# UART_CHANGER.net
KiCad netlist of a schematic drawn in Altium Designer
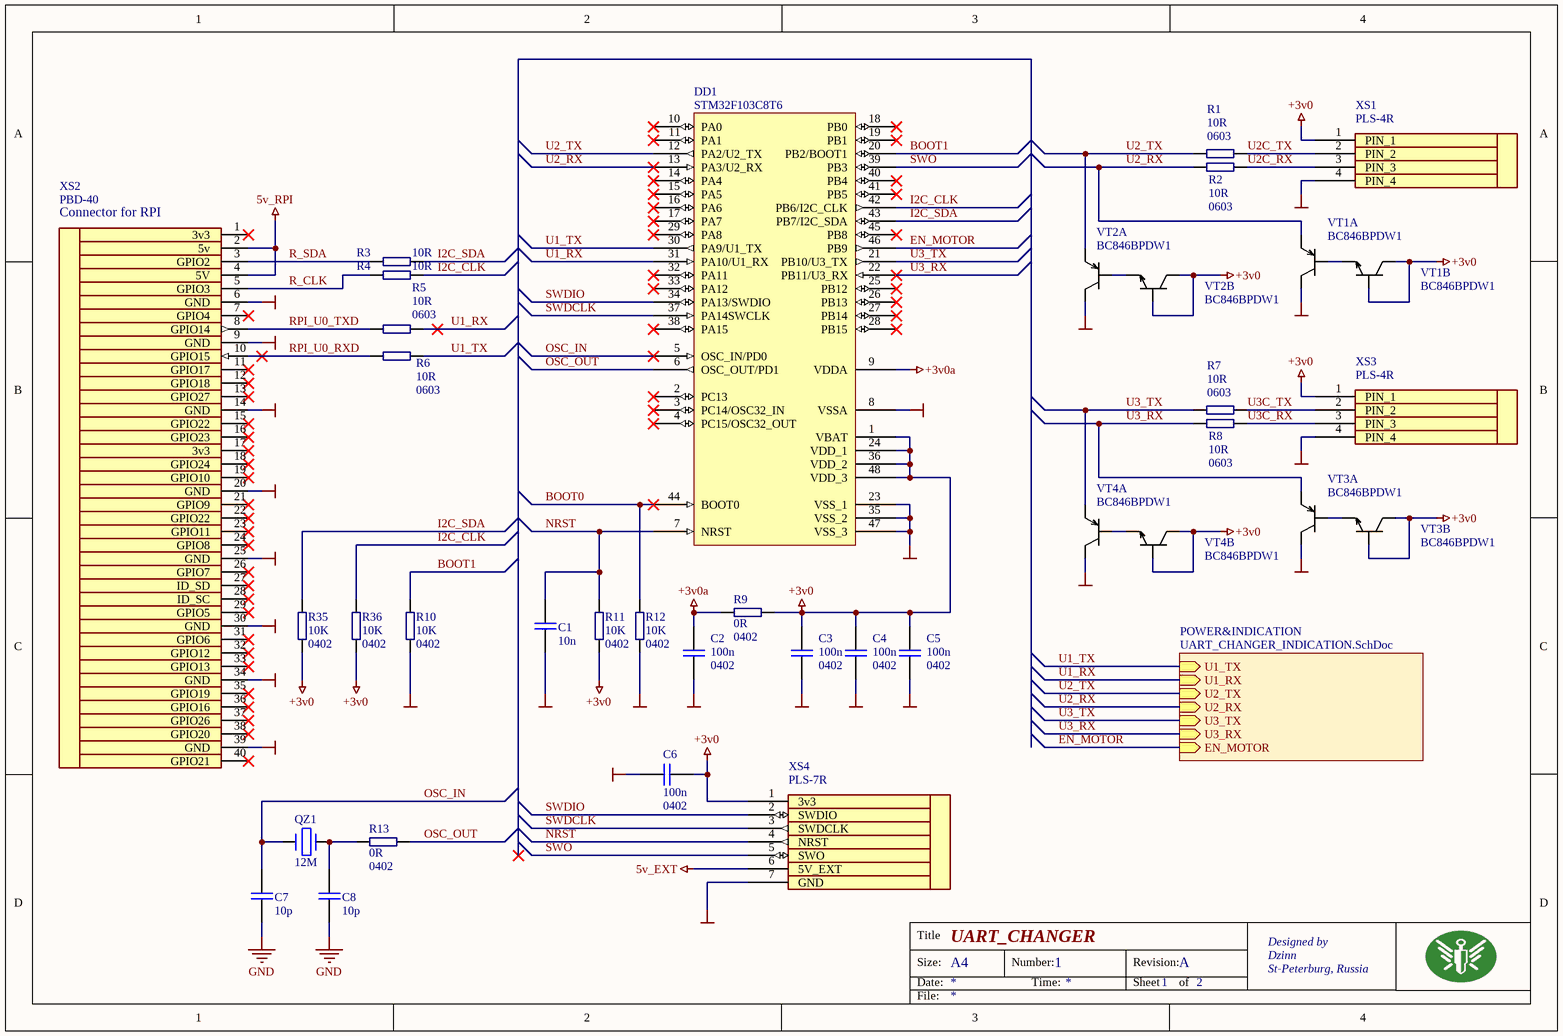
[diagram p0: UART_CHANGER.SchDoc]

(export (version "E")
  (design (tool "Eeschema 10.0.6"))
  (components
    (comp (ref "C1")
      (value "10n")
      (footprint "0402")
      (description "CAP 0402 100n")
      (fields
        (field (name "PART NUMBER") "C000001")
        (field (name "MANUFACTURER") "Murata")
        (field (name "CHECK FOOTPRINT") "A")
        (field (name "CHECK SYMBOL") "A")
      )
      (libsource (lib "Dzinn_lib") (part "CAP_NP"))
    )
    (comp (ref "C2")
      (value "100n")
      (footprint "0402")
      (description "CAP 0402 100n")
      (fields
        (field (name "PART NUMBER") "C000001")
        (field (name "MANUFACTURER") "Murata")
        (field (name "PACKAGE") "0402")
        (field (name "CHECK FOOTPRINT") "A")
        (field (name "CHECK SYMBOL") "A")
      )
      (libsource (lib "Dzinn_lib") (part "CAP_NP"))
    )
    (comp (ref "C3")
      (value "100n")
      (footprint "0402")
      (description "CAP 0402 100n")
      (fields
        (field (name "PART NUMBER") "C000001")
        (field (name "MANUFACTURER") "Murata")
        (field (name "PACKAGE") "0402")
        (field (name "CHECK FOOTPRINT") "A")
        (field (name "CHECK SYMBOL") "A")
      )
      (libsource (lib "Dzinn_lib") (part "CAP_NP"))
    )
    (comp (ref "C4")
      (value "100n")
      (footprint "0402")
      (description "CAP 0402 100n")
      (fields
        (field (name "PART NUMBER") "C000001")
        (field (name "MANUFACTURER") "Murata")
        (field (name "PACKAGE") "0402")
        (field (name "CHECK FOOTPRINT") "A")
        (field (name "CHECK SYMBOL") "A")
      )
      (libsource (lib "Dzinn_lib") (part "CAP_NP"))
    )
    (comp (ref "C5")
      (value "100n")
      (footprint "0402")
      (description "CAP 0402 100n")
      (fields
        (field (name "PART NUMBER") "C000001")
        (field (name "MANUFACTURER") "Murata")
        (field (name "PACKAGE") "0402")
        (field (name "CHECK FOOTPRINT") "A")
        (field (name "CHECK SYMBOL") "A")
      )
      (libsource (lib "Dzinn_lib") (part "CAP_NP"))
    )
    (comp (ref "C6")
      (value "100n")
      (footprint "0402")
      (description "CAP 0402 100n")
      (fields
        (field (name "PART NUMBER") "C000001")
        (field (name "MANUFACTURER") "Murata")
        (field (name "PACKAGE") "0402")
        (field (name "CHECK FOOTPRINT") "A")
        (field (name "CHECK SYMBOL") "A")
      )
      (libsource (lib "Dzinn_lib") (part "CAP_NP"))
    )
    (comp (ref "C7")
      (value "10p")
      (footprint "0402")
      (description "CAP 0402 100n")
      (fields
        (field (name "PART NUMBER") "C000001")
        (field (name "MANUFACTURER") "Murata")
        (field (name "CHECK FOOTPRINT") "A")
        (field (name "CHECK SYMBOL") "A")
      )
      (libsource (lib "Dzinn_lib") (part "CAP_NP"))
    )
    (comp (ref "C8")
      (value "10p")
      (footprint "0402")
      (description "CAP 0402 100n")
      (fields
        (field (name "PART NUMBER") "C000001")
        (field (name "MANUFACTURER") "Murata")
        (field (name "CHECK FOOTPRINT") "A")
        (field (name "CHECK SYMBOL") "A")
      )
      (libsource (lib "Dzinn_lib") (part "CAP_NP"))
    )
    (comp (ref "DD1")
      (value "STM32F103С8T6")
      (footprint "LQFP-48-ST")
      (description "32 Bit 72Mhz ARM MCU")
      (fields
        (field (name "PART NUMBER") "U00026")
        (field (name "MANUFACTURER") "ST")
        (field (name "CHECK FOOTPRINT") "A")
        (field (name "CHECK SYMBOL") "A")
      )
      (libsource (lib "Dzinn_lib") (part "STM32F103С8T6"))
    )
    (comp (ref "QZ1")
      (value "12M")
      (footprint "DSX221G")
      (description "12M SMD QUARTZ")
      (fields
        (field (name "PART NUMBER") "QZ00002")
        (field (name "MANUFACTURER") "NDK")
        (field (name "CHECK FOOTPRINT") "A")
        (field (name "CHECK SYMBOL") "A")
      )
      (libsource (lib "Dzinn_lib") (part "Quartz-NP"))
    )
    (comp (ref "R1")
      (value "10R")
      (footprint "0603")
      (description "RES SMD")
      (fields
        (field (name "PART NUMBER") "R000195")
        (field (name "MANUFACTURER") "Rohm Semiconductor")
        (field (name "PACKAGE") "0603")
        (field (name "CHECK FOOTPRINT") "A")
        (field (name "CHECK SYMBOL") "A")
      )
      (libsource (lib "Dzinn_lib") (part "RES"))
    )
    (comp (ref "R2")
      (value "10R")
      (footprint "0603")
      (description "RES SMD")
      (fields
        (field (name "PART NUMBER") "R000195")
        (field (name "MANUFACTURER") "Rohm Semiconductor")
        (field (name "PACKAGE") "0603")
        (field (name "CHECK FOOTPRINT") "A")
        (field (name "CHECK SYMBOL") "A")
      )
      (libsource (lib "Dzinn_lib") (part "RES"))
    )
    (comp (ref "R3")
      (value "10R")
      (footprint "0603")
      (description "RES SMD")
      (fields
        (field (name "PART NUMBER") "R000195")
        (field (name "MANUFACTURER") "Rohm Semiconductor")
        (field (name "CHECK FOOTPRINT") "A")
        (field (name "CHECK SYMBOL") "A")
      )
      (libsource (lib "Dzinn_lib") (part "RES"))
    )
    (comp (ref "R4")
      (value "10R")
      (footprint "0603")
      (description "RES SMD")
      (fields
        (field (name "PART NUMBER") "R000195")
        (field (name "MANUFACTURER") "Rohm Semiconductor")
        (field (name "CHECK FOOTPRINT") "A")
        (field (name "CHECK SYMBOL") "A")
      )
      (libsource (lib "Dzinn_lib") (part "RES"))
    )
    (comp (ref "R5")
      (value "10R")
      (footprint "0603")
      (description "RES SMD")
      (fields
        (field (name "PART NUMBER") "R000195")
        (field (name "MANUFACTURER") "Rohm Semiconductor")
        (field (name "PACKAGE") "0603")
        (field (name "CHECK FOOTPRINT") "A")
        (field (name "CHECK SYMBOL") "A")
      )
      (libsource (lib "Dzinn_lib") (part "RES"))
    )
    (comp (ref "R6")
      (value "10R")
      (footprint "0603")
      (description "RES SMD")
      (fields
        (field (name "PART NUMBER") "R000195")
        (field (name "MANUFACTURER") "Rohm Semiconductor")
        (field (name "PACKAGE") "0603")
        (field (name "CHECK FOOTPRINT") "A")
        (field (name "CHECK SYMBOL") "A")
      )
      (libsource (lib "Dzinn_lib") (part "RES"))
    )
    (comp (ref "R7")
      (value "10R")
      (footprint "0603")
      (description "RES SMD")
      (fields
        (field (name "PART NUMBER") "R000195")
        (field (name "MANUFACTURER") "Rohm Semiconductor")
        (field (name "PACKAGE") "0603")
        (field (name "CHECK FOOTPRINT") "A")
        (field (name "CHECK SYMBOL") "A")
      )
      (libsource (lib "Dzinn_lib") (part "RES"))
    )
    (comp (ref "R8")
      (value "10R")
      (footprint "0603")
      (description "RES SMD")
      (fields
        (field (name "PART NUMBER") "R000195")
        (field (name "MANUFACTURER") "Rohm Semiconductor")
        (field (name "PACKAGE") "0603")
        (field (name "CHECK FOOTPRINT") "A")
        (field (name "CHECK SYMBOL") "A")
      )
      (libsource (lib "Dzinn_lib") (part "RES"))
    )
    (comp (ref "R9")
      (value "0R")
      (footprint "0402")
      (description "RES SMD")
      (fields
        (field (name "PART NUMBER") "R000001")
        (field (name "MANUFACTURER") "Rohm Semiconductor")
        (field (name "PACKAGE") "0402")
        (field (name "CHECK FOOTPRINT") "A")
        (field (name "CHECK SYMBOL") "A")
      )
      (libsource (lib "Dzinn_lib") (part "RES"))
    )
    (comp (ref "R10")
      (value "10K")
      (footprint "0402")
      (description "RES SMD")
      (fields
        (field (name "PART NUMBER") "R000098")
        (field (name "MANUFACTURER") "Rohm Semiconductor")
        (field (name "PACKAGE") "0402")
        (field (name "CHECK FOOTPRINT") "A")
        (field (name "CHECK SYMBOL") "A")
      )
      (libsource (lib "Dzinn_lib") (part "RES"))
    )
    (comp (ref "R11")
      (value "10K")
      (footprint "0402")
      (description "RES SMD")
      (fields
        (field (name "PART NUMBER") "R000098")
        (field (name "MANUFACTURER") "Rohm Semiconductor")
        (field (name "PACKAGE") "0402")
        (field (name "CHECK FOOTPRINT") "A")
        (field (name "CHECK SYMBOL") "A")
      )
      (libsource (lib "Dzinn_lib") (part "RES"))
    )
    (comp (ref "R12")
      (value "10K")
      (footprint "0402")
      (description "RES SMD")
      (fields
        (field (name "PART NUMBER") "R000098")
        (field (name "MANUFACTURER") "Rohm Semiconductor")
        (field (name "PACKAGE") "0402")
        (field (name "CHECK FOOTPRINT") "A")
        (field (name "CHECK SYMBOL") "A")
      )
      (libsource (lib "Dzinn_lib") (part "RES"))
    )
    (comp (ref "R13")
      (value "0R")
      (footprint "0402")
      (description "RES SMD")
      (fields
        (field (name "PART NUMBER") "R000001")
        (field (name "MANUFACTURER") "Rohm Semiconductor")
        (field (name "PACKAGE") "0402")
        (field (name "CHECK FOOTPRINT") "A")
        (field (name "CHECK SYMBOL") "A")
      )
      (libsource (lib "Dzinn_lib") (part "RES"))
    )
    (comp (ref "R35")
      (value "10K")
      (footprint "0402")
      (description "RES SMD")
      (fields
        (field (name "PART NUMBER") "R000098")
        (field (name "MANUFACTURER") "Rohm Semiconductor")
        (field (name "PACKAGE") "0402")
        (field (name "CHECK FOOTPRINT") "A")
        (field (name "CHECK SYMBOL") "A")
      )
      (libsource (lib "Dzinn_lib") (part "RES"))
    )
    (comp (ref "R36")
      (value "10K")
      (footprint "0402")
      (description "RES SMD")
      (fields
        (field (name "PART NUMBER") "R000098")
        (field (name "MANUFACTURER") "Rohm Semiconductor")
        (field (name "PACKAGE") "0402")
        (field (name "CHECK FOOTPRINT") "A")
        (field (name "CHECK SYMBOL") "A")
      )
      (libsource (lib "Dzinn_lib") (part "RES"))
    )
    (comp (ref "VT1")
      (value "BC846BPDW1")
      (footprint "SOT-363")
      (description "60V 100mA PNP/NPN Transistor")
      (fields
        (field (name "PART NUMBER") "VT00002")
        (field (name "MANUFACTURER") "ON")
        (field (name "CHECK FOOTPRINT") "A")
        (field (name "CHECK SYMBOL") "A")
      )
      (libsource (lib "Dzinn_lib") (part "PNP/NPN"))
    )
    (comp (ref "VT2")
      (value "BC846BPDW1")
      (footprint "SOT-363")
      (description "60V 100mA PNP/NPN Transistor")
      (fields
        (field (name "PART NUMBER") "VT00002")
        (field (name "MANUFACTURER") "ON")
        (field (name "CHECK FOOTPRINT") "A")
        (field (name "CHECK SYMBOL") "A")
      )
      (libsource (lib "Dzinn_lib") (part "PNP/NPN"))
    )
    (comp (ref "VT3")
      (value "BC846BPDW1")
      (footprint "SOT-363")
      (description "60V 100mA PNP/NPN Transistor")
      (fields
        (field (name "PART NUMBER") "VT00002")
        (field (name "MANUFACTURER") "ON")
        (field (name "CHECK FOOTPRINT") "A")
        (field (name "CHECK SYMBOL") "A")
      )
      (libsource (lib "Dzinn_lib") (part "PNP/NPN"))
    )
    (comp (ref "VT4")
      (value "BC846BPDW1")
      (footprint "SOT-363")
      (description "60V 100mA PNP/NPN Transistor")
      (fields
        (field (name "PART NUMBER") "VT00002")
        (field (name "MANUFACTURER") "ON")
        (field (name "CHECK FOOTPRINT") "A")
        (field (name "CHECK SYMBOL") "A")
      )
      (libsource (lib "Dzinn_lib") (part "PNP/NPN"))
    )
    (comp (ref "XS1")
      (value "PLS-4R")
      (footprint "PLS-4R")
      (description "4 PIN PLS right angle")
      (fields
        (field (name "PART NUMBER") "XS00013")
        (field (name "MANUFACTURER") "WE")
        (field (name "CHECK FOOTPRINT") "A")
        (field (name "CHECK SYMBOL") "A")
      )
      (libsource (lib "Dzinn_lib") (part "4_PIN_CON"))
    )
    (comp (ref "XS2")
      (value "PBD-40")
      (footprint "PBВ-40")
      (fields
        (field (name "PART NUMBER") "XS00012")
        (field (name "CHECK FOOTPRINT") "A")
        (field (name "CHECK SYMBOL") "A")
      )
      (libsource (lib "Dzinn_lib") (part "40_PIN_CON"))
    )
    (comp (ref "XS3")
      (value "PLS-4R")
      (footprint "PLS-4R")
      (description "4 PIN PLS right angle")
      (fields
        (field (name "PART NUMBER") "XS00013")
        (field (name "MANUFACTURER") "WE")
        (field (name "CHECK FOOTPRINT") "A")
        (field (name "CHECK SYMBOL") "A")
      )
      (libsource (lib "Dzinn_lib") (part "4_PIN_CON"))
    )
    (comp (ref "XS4")
      (value "PLS-7R")
      (footprint "PLS-7R")
      (description "7 PIN PLS right angle")
      (fields
        (field (name "PART NUMBER") "XS00003")
        (field (name "MANUFACTURER") "TE")
        (field (name "CHECK FOOTPRINT") "A")
        (field (name "CHECK SYMBOL") "A")
      )
      (libsource (lib "Dzinn_lib") (part "7_PIN_CON"))
    )
  )
  (nets
    (net (code "1") (name "+3v0") (class "Default")
      (node (ref "C3") (pin "1") (pinfunction "1_1") (pintype "passive"))
      (node (ref "C4") (pin "1") (pinfunction "1_1") (pintype "passive"))
      (node (ref "C5") (pin "1") (pinfunction "1_1") (pintype "passive"))
      (node (ref "C6") (pin "2") (pinfunction "2_2") (pintype "passive"))
      (node (ref "DD1") (pin "1") (pinfunction "VBAT_1") (pintype "power_in"))
      (node (ref "DD1") (pin "24") (pinfunction "VDD_1_24") (pintype "power_in"))
      (node (ref "DD1") (pin "36") (pinfunction "VDD_2_36") (pintype "power_in"))
      (node (ref "DD1") (pin "48") (pinfunction "VDD_3_48") (pintype "power_in"))
      (node (ref "R11") (pin "1") (pinfunction "1_1") (pintype "passive"))
      (node (ref "R35") (pin "1") (pinfunction "1_1") (pintype "passive"))
      (node (ref "R36") (pin "1") (pinfunction "1_1") (pintype "passive"))
      (node (ref "R9") (pin "1") (pinfunction "1_1") (pintype "passive"))
      (node (ref "VT1") (pin "2") (pinfunction "2_2") (pintype "passive"))
      (node (ref "VT1") (pin "6") (pinfunction "6_6") (pintype "passive"))
      (node (ref "VT2") (pin "2") (pinfunction "2_2") (pintype "passive"))
      (node (ref "VT2") (pin "6") (pinfunction "6_6") (pintype "passive"))
      (node (ref "VT3") (pin "2") (pinfunction "2_2") (pintype "passive"))
      (node (ref "VT3") (pin "6") (pinfunction "6_6") (pintype "passive"))
      (node (ref "VT4") (pin "2") (pinfunction "2_2") (pintype "passive"))
      (node (ref "VT4") (pin "6") (pinfunction "6_6") (pintype "passive"))
      (node (ref "XS1") (pin "1") (pinfunction "PIN_1_1") (pintype "passive"))
      (node (ref "XS3") (pin "1") (pinfunction "PIN_1_1") (pintype "passive"))
      (node (ref "XS4") (pin "1") (pinfunction "3v3_1") (pintype "passive"))
    )
    (net (code "2") (name "+3v0a") (class "Default")
      (node (ref "C2") (pin "1") (pinfunction "1_1") (pintype "passive"))
      (node (ref "DD1") (pin "9") (pinfunction "VDDA_9") (pintype "power_in"))
      (node (ref "R9") (pin "2") (pinfunction "2_2") (pintype "passive"))
    )
    (net (code "3") (name "/BOOT0") (class "Default")
      (node (ref "DD1") (pin "44") (pinfunction "BOOT0_44") (pintype "input"))
      (node (ref "R12") (pin "2") (pinfunction "2_2") (pintype "passive"))
    )
    (net (code "4") (name "/BOOT1") (class "Default")
      (node (ref "DD1") (pin "20") (pinfunction "PB2/BOOT1_20") (pintype "bidirectional"))
      (node (ref "R10") (pin "2") (pinfunction "2_2") (pintype "passive"))
    )
    (net (code "5") (name "/EN_MOTOR") (class "Default")
      (node (ref "DD1") (pin "46") (pinfunction "PB9_46") (pintype "output"))
    )
    (net (code "6") (name "/I2C_CLK") (class "Default")
      (node (ref "DD1") (pin "42") (pinfunction "PB6/I2C_CLK_42") (pintype "output"))
      (node (ref "R36") (pin "2") (pinfunction "2_2") (pintype "passive"))
      (node (ref "R4") (pin "1") (pinfunction "1_1") (pintype "passive"))
    )
    (net (code "7") (name "/I2C_SDA") (class "Default")
      (node (ref "DD1") (pin "43") (pinfunction "PB7/I2C_SDA_43") (pintype "bidirectional"))
      (node (ref "R3") (pin "1") (pinfunction "1_1") (pintype "passive"))
      (node (ref "R35") (pin "2") (pinfunction "2_2") (pintype "passive"))
    )
    (net (code "8") (name "/NRST") (class "Default")
      (node (ref "C1") (pin "1") (pinfunction "1_1") (pintype "passive"))
      (node (ref "DD1") (pin "7") (pinfunction "NRST_7") (pintype "input"))
      (node (ref "R11") (pin "2") (pinfunction "2_2") (pintype "passive"))
      (node (ref "XS4") (pin "4") (pinfunction "NRST_4") (pintype "output"))
    )
    (net (code "9") (name "/OSC_IN") (class "Default")
      (node (ref "C7") (pin "1") (pinfunction "1_1") (pintype "passive"))
      (node (ref "DD1") (pin "5") (pinfunction "OSC_IN/PD0_5") (pintype "input"))
      (node (ref "QZ1") (pin "3") (pinfunction "3_3") (pintype "passive"))
    )
    (net (code "10") (name "/OSC_OUT") (class "Default")
      (node (ref "DD1") (pin "6") (pinfunction "OSC_OUT/PD1_6") (pintype "output"))
      (node (ref "R13") (pin "1") (pinfunction "1_1") (pintype "passive"))
    )
    (net (code "11") (name "/RPI_U0_RXD") (class "Default")
      (node (ref "R6") (pin "2") (pinfunction "2_2") (pintype "passive"))
      (node (ref "XS2") (pin "10") (pinfunction "GPIO15_10") (pintype "input"))
    )
    (net (code "12") (name "/RPI_U0_TXD") (class "Default")
      (node (ref "R5") (pin "2") (pinfunction "2_2") (pintype "passive"))
      (node (ref "XS2") (pin "8") (pinfunction "GPIO14_8") (pintype "output"))
    )
    (net (code "13") (name "/R_CLK") (class "Default")
      (node (ref "R4") (pin "2") (pinfunction "2_2") (pintype "passive"))
      (node (ref "XS2") (pin "5") (pinfunction "GPIO3_5") (pintype "passive"))
    )
    (net (code "14") (name "/R_SDA") (class "Default")
      (node (ref "R3") (pin "2") (pinfunction "2_2") (pintype "passive"))
      (node (ref "XS2") (pin "3") (pinfunction "GPIO2_3") (pintype "passive"))
    )
    (net (code "15") (name "/SWDCLK") (class "Default")
      (node (ref "DD1") (pin "37") (pinfunction "PA14SWCLK_37") (pintype "input"))
      (node (ref "XS4") (pin "3") (pinfunction "SWDCLK_3") (pintype "output"))
    )
    (net (code "16") (name "/SWDIO") (class "Default")
      (node (ref "DD1") (pin "34") (pinfunction "PA13/SWDIO_34") (pintype "bidirectional"))
      (node (ref "XS4") (pin "2") (pinfunction "SWDIO_2") (pintype "bidirectional"))
    )
    (net (code "17") (name "/SWO") (class "Default")
      (node (ref "DD1") (pin "39") (pinfunction "PB3_39") (pintype "bidirectional"))
      (node (ref "XS4") (pin "5") (pinfunction "SWO_5") (pintype "bidirectional"))
    )
    (net (code "18") (name "/U1_RX") (class "Default")
      (node (ref "DD1") (pin "31") (pinfunction "PA10/U1_RX_31") (pintype "input"))
      (node (ref "R5") (pin "1") (pinfunction "1_1") (pintype "passive"))
    )
    (net (code "19") (name "/U1_TX") (class "Default")
      (node (ref "DD1") (pin "30") (pinfunction "PA9/U1_TX_30") (pintype "output"))
      (node (ref "R6") (pin "1") (pinfunction "1_1") (pintype "passive"))
    )
    (net (code "20") (name "/U2C_RX") (class "Default")
      (node (ref "R2") (pin "1") (pinfunction "1_1") (pintype "passive"))
      (node (ref "XS1") (pin "3") (pinfunction "PIN_3_3") (pintype "passive"))
    )
    (net (code "21") (name "/U2C_TX") (class "Default")
      (node (ref "R1") (pin "1") (pinfunction "1_1") (pintype "passive"))
      (node (ref "XS1") (pin "2") (pinfunction "PIN_2_2") (pintype "passive"))
    )
    (net (code "22") (name "/U2_RX") (class "Default")
      (node (ref "DD1") (pin "13") (pinfunction "PA3/U2_RX_13") (pintype "input"))
      (node (ref "R2") (pin "2") (pinfunction "2_2") (pintype "passive"))
      (node (ref "VT1") (pin "4") (pinfunction "4_4") (pintype "passive"))
    )
    (net (code "23") (name "/U2_TX") (class "Default")
      (node (ref "DD1") (pin "12") (pinfunction "PA2/U2_TX_12") (pintype "output"))
      (node (ref "R1") (pin "2") (pinfunction "2_2") (pintype "passive"))
      (node (ref "VT2") (pin "4") (pinfunction "4_4") (pintype "passive"))
    )
    (net (code "24") (name "/U3C_RX") (class "Default")
      (node (ref "R8") (pin "1") (pinfunction "1_1") (pintype "passive"))
      (node (ref "XS3") (pin "3") (pinfunction "PIN_3_3") (pintype "passive"))
    )
    (net (code "25") (name "/U3C_TX") (class "Default")
      (node (ref "R7") (pin "1") (pinfunction "1_1") (pintype "passive"))
      (node (ref "XS3") (pin "2") (pinfunction "PIN_2_2") (pintype "passive"))
    )
    (net (code "26") (name "/U3_RX") (class "Default")
      (node (ref "DD1") (pin "22") (pinfunction "PB11/U3_RX_22") (pintype "input"))
      (node (ref "R8") (pin "2") (pinfunction "2_2") (pintype "passive"))
      (node (ref "VT3") (pin "4") (pinfunction "4_4") (pintype "passive"))
    )
    (net (code "27") (name "/U3_TX") (class "Default")
      (node (ref "DD1") (pin "21") (pinfunction "PB10/U3_TX_21") (pintype "output"))
      (node (ref "R7") (pin "2") (pinfunction "2_2") (pintype "passive"))
      (node (ref "VT4") (pin "4") (pinfunction "4_4") (pintype "passive"))
    )
    (net (code "28") (name "5v_EXT") (class "Default")
      (node (ref "XS4") (pin "6") (pinfunction "5V_EXT_6") (pintype "passive"))
    )
    (net (code "29") (name "5v_RPI") (class "Default")
      (node (ref "XS2") (pin "2") (pinfunction "5v_2") (pintype "passive"))
      (node (ref "XS2") (pin "4") (pinfunction "5V_4") (pintype "passive"))
    )
    (net (code "30") (name "GND") (class "Default")
      (node (ref "C1") (pin "2") (pinfunction "2_2") (pintype "passive"))
      (node (ref "C2") (pin "2") (pinfunction "2_2") (pintype "passive"))
      (node (ref "C3") (pin "2") (pinfunction "2_2") (pintype "passive"))
      (node (ref "C4") (pin "2") (pinfunction "2_2") (pintype "passive"))
      (node (ref "C5") (pin "2") (pinfunction "2_2") (pintype "passive"))
      (node (ref "C6") (pin "1") (pinfunction "1_1") (pintype "passive"))
      (node (ref "C7") (pin "2") (pinfunction "2_2") (pintype "passive"))
      (node (ref "C8") (pin "2") (pinfunction "2_2") (pintype "passive"))
      (node (ref "DD1") (pin "23") (pinfunction "VSS_1_23") (pintype "power_in"))
      (node (ref "DD1") (pin "35") (pinfunction "VSS_2_35") (pintype "power_in"))
      (node (ref "DD1") (pin "47") (pinfunction "VSS_3_47") (pintype "power_in"))
      (node (ref "DD1") (pin "8") (pinfunction "VSSA_8") (pintype "power_in"))
      (node (ref "R10") (pin "1") (pinfunction "1_1") (pintype "passive"))
      (node (ref "R12") (pin "1") (pinfunction "1_1") (pintype "passive"))
      (node (ref "VT1") (pin "3") (pinfunction "3_3") (pintype "passive"))
      (node (ref "VT2") (pin "3") (pinfunction "3_3") (pintype "passive"))
      (node (ref "VT3") (pin "3") (pinfunction "3_3") (pintype "passive"))
      (node (ref "VT4") (pin "3") (pinfunction "3_3") (pintype "passive"))
      (node (ref "XS1") (pin "4") (pinfunction "PIN_4_4") (pintype "passive"))
      (node (ref "XS2") (pin "14") (pinfunction "GND_14") (pintype "passive"))
      (node (ref "XS2") (pin "20") (pinfunction "GND_20") (pintype "passive"))
      (node (ref "XS2") (pin "25") (pinfunction "GND_25") (pintype "passive"))
      (node (ref "XS2") (pin "30") (pinfunction "GND_30") (pintype "passive"))
      (node (ref "XS2") (pin "34") (pinfunction "GND_34") (pintype "passive"))
      (node (ref "XS2") (pin "39") (pinfunction "GND_39") (pintype "passive"))
      (node (ref "XS2") (pin "6") (pinfunction "GND_6") (pintype "passive"))
      (node (ref "XS2") (pin "9") (pinfunction "GND_9") (pintype "passive"))
      (node (ref "XS3") (pin "4") (pinfunction "PIN_4_4") (pintype "passive"))
      (node (ref "XS4") (pin "7") (pinfunction "GND_7") (pintype "passive"))
    )
    (net (code "31") (name "Net-(C8-Pad1)") (class "Default")
      (node (ref "C8") (pin "1") (pinfunction "1_1") (pintype "passive"))
      (node (ref "QZ1") (pin "1") (pinfunction "1_1") (pintype "passive"))
      (node (ref "R13") (pin "2") (pinfunction "2_2") (pintype "passive"))
    )
    (net (code "32") (name "Net-(VT1-Pad1)") (class "Default")
      (node (ref "VT1") (pin "1") (pinfunction "1_1") (pintype "passive"))
      (node (ref "VT1") (pin "5") (pinfunction "5_5") (pintype "passive"))
    )
    (net (code "33") (name "Net-(VT2-Pad1)") (class "Default")
      (node (ref "VT2") (pin "1") (pinfunction "1_1") (pintype "passive"))
      (node (ref "VT2") (pin "5") (pinfunction "5_5") (pintype "passive"))
    )
    (net (code "34") (name "Net-(VT3-Pad1)") (class "Default")
      (node (ref "VT3") (pin "1") (pinfunction "1_1") (pintype "passive"))
      (node (ref "VT3") (pin "5") (pinfunction "5_5") (pintype "passive"))
    )
    (net (code "35") (name "Net-(VT4-Pad1)") (class "Default")
      (node (ref "VT4") (pin "1") (pinfunction "1_1") (pintype "passive"))
      (node (ref "VT4") (pin "5") (pinfunction "5_5") (pintype "passive"))
    )
    (net (code "36") (name "unconnected-(DD1-PA0-Pad10)") (class "Default")
      (node (ref "DD1") (pin "10") (pinfunction "PA0_10") (pintype "bidirectional+no_connect"))
    )
    (net (code "37") (name "unconnected-(DD1-PA1-Pad11)") (class "Default")
      (node (ref "DD1") (pin "11") (pinfunction "PA1_11") (pintype "bidirectional+no_connect"))
    )
    (net (code "38") (name "unconnected-(DD1-PA4-Pad14)") (class "Default")
      (node (ref "DD1") (pin "14") (pinfunction "PA4_14") (pintype "bidirectional+no_connect"))
    )
    (net (code "39") (name "unconnected-(DD1-PA5-Pad15)") (class "Default")
      (node (ref "DD1") (pin "15") (pinfunction "PA5_15") (pintype "bidirectional+no_connect"))
    )
    (net (code "40") (name "unconnected-(DD1-PA6-Pad16)") (class "Default")
      (node (ref "DD1") (pin "16") (pinfunction "PA6_16") (pintype "bidirectional+no_connect"))
    )
    (net (code "41") (name "unconnected-(DD1-PA7-Pad17)") (class "Default")
      (node (ref "DD1") (pin "17") (pinfunction "PA7_17") (pintype "bidirectional+no_connect"))
    )
    (net (code "42") (name "unconnected-(DD1-PA8-Pad29)") (class "Default")
      (node (ref "DD1") (pin "29") (pinfunction "PA8_29") (pintype "bidirectional+no_connect"))
    )
    (net (code "43") (name "unconnected-(DD1-PA11-Pad32)") (class "Default")
      (node (ref "DD1") (pin "32") (pinfunction "PA11_32") (pintype "bidirectional+no_connect"))
    )
    (net (code "44") (name "unconnected-(DD1-PA12-Pad33)") (class "Default")
      (node (ref "DD1") (pin "33") (pinfunction "PA12_33") (pintype "bidirectional+no_connect"))
    )
    (net (code "45") (name "unconnected-(DD1-PA15-Pad38)") (class "Default")
      (node (ref "DD1") (pin "38") (pinfunction "PA15_38") (pintype "bidirectional+no_connect"))
    )
    (net (code "46") (name "unconnected-(DD1-PB0-Pad18)") (class "Default")
      (node (ref "DD1") (pin "18") (pinfunction "PB0_18") (pintype "bidirectional+no_connect"))
    )
    (net (code "47") (name "unconnected-(DD1-PB1-Pad19)") (class "Default")
      (node (ref "DD1") (pin "19") (pinfunction "PB1_19") (pintype "bidirectional+no_connect"))
    )
    (net (code "48") (name "unconnected-(DD1-PB4-Pad40)") (class "Default")
      (node (ref "DD1") (pin "40") (pinfunction "PB4_40") (pintype "bidirectional+no_connect"))
    )
    (net (code "49") (name "unconnected-(DD1-PB5-Pad41)") (class "Default")
      (node (ref "DD1") (pin "41") (pinfunction "PB5_41") (pintype "bidirectional+no_connect"))
    )
    (net (code "50") (name "unconnected-(DD1-PB8-Pad45)") (class "Default")
      (node (ref "DD1") (pin "45") (pinfunction "PB8_45") (pintype "bidirectional+no_connect"))
    )
    (net (code "51") (name "unconnected-(DD1-PB12-Pad25)") (class "Default")
      (node (ref "DD1") (pin "25") (pinfunction "PB12_25") (pintype "bidirectional+no_connect"))
    )
    (net (code "52") (name "unconnected-(DD1-PB13-Pad26)") (class "Default")
      (node (ref "DD1") (pin "26") (pinfunction "PB13_26") (pintype "bidirectional+no_connect"))
    )
    (net (code "53") (name "unconnected-(DD1-PB14-Pad27)") (class "Default")
      (node (ref "DD1") (pin "27") (pinfunction "PB14_27") (pintype "bidirectional+no_connect"))
    )
    (net (code "54") (name "unconnected-(DD1-PB15-Pad28)") (class "Default")
      (node (ref "DD1") (pin "28") (pinfunction "PB15_28") (pintype "bidirectional+no_connect"))
    )
    (net (code "55") (name "unconnected-(DD1-PC13-Pad2)") (class "Default")
      (node (ref "DD1") (pin "2") (pinfunction "PC13_2") (pintype "bidirectional+no_connect"))
    )
    (net (code "56") (name "unconnected-(DD1-PC14{slash}OSC32_IN-Pad3)") (class "Default")
      (node (ref "DD1") (pin "3") (pinfunction "PC14/OSC32_IN_3") (pintype "bidirectional+no_connect"))
    )
    (net (code "57") (name "unconnected-(DD1-PC15{slash}OSC32_OUT-Pad4)") (class "Default")
      (node (ref "DD1") (pin "4") (pinfunction "PC15/OSC32_OUT_4") (pintype "bidirectional+no_connect"))
    )
    (net (code "58") (name "unconnected-(XS2-3v3-Pad1)") (class "Default")
      (node (ref "XS2") (pin "1") (pinfunction "3v3_1") (pintype "passive+no_connect"))
    )
    (net (code "59") (name "unconnected-(XS2-3v3-Pad17)") (class "Default")
      (node (ref "XS2") (pin "17") (pinfunction "3v3_17") (pintype "passive+no_connect"))
    )
    (net (code "60") (name "unconnected-(XS2-GPIO4-Pad7)") (class "Default")
      (node (ref "XS2") (pin "7") (pinfunction "GPIO4_7") (pintype "passive+no_connect"))
    )
    (net (code "61") (name "unconnected-(XS2-GPIO5-Pad29)") (class "Default")
      (node (ref "XS2") (pin "29") (pinfunction "GPIO5_29") (pintype "passive+no_connect"))
    )
    (net (code "62") (name "unconnected-(XS2-GPIO6-Pad31)") (class "Default")
      (node (ref "XS2") (pin "31") (pinfunction "GPIO6_31") (pintype "passive+no_connect"))
    )
    (net (code "63") (name "unconnected-(XS2-GPIO7-Pad26)") (class "Default")
      (node (ref "XS2") (pin "26") (pinfunction "GPIO7_26") (pintype "passive+no_connect"))
    )
    (net (code "64") (name "unconnected-(XS2-GPIO8-Pad24)") (class "Default")
      (node (ref "XS2") (pin "24") (pinfunction "GPIO8_24") (pintype "passive+no_connect"))
    )
    (net (code "65") (name "unconnected-(XS2-GPIO9-Pad21)") (class "Default")
      (node (ref "XS2") (pin "21") (pinfunction "GPIO9_21") (pintype "passive+no_connect"))
    )
    (net (code "66") (name "unconnected-(XS2-GPIO10-Pad19)") (class "Default")
      (node (ref "XS2") (pin "19") (pinfunction "GPIO10_19") (pintype "passive+no_connect"))
    )
    (net (code "67") (name "unconnected-(XS2-GPIO11-Pad23)") (class "Default")
      (node (ref "XS2") (pin "23") (pinfunction "GPIO11_23") (pintype "passive+no_connect"))
    )
    (net (code "68") (name "unconnected-(XS2-GPIO12-Pad32)") (class "Default")
      (node (ref "XS2") (pin "32") (pinfunction "GPIO12_32") (pintype "passive+no_connect"))
    )
    (net (code "69") (name "unconnected-(XS2-GPIO13-Pad33)") (class "Default")
      (node (ref "XS2") (pin "33") (pinfunction "GPIO13_33") (pintype "passive+no_connect"))
    )
    (net (code "70") (name "unconnected-(XS2-GPIO16-Pad36)") (class "Default")
      (node (ref "XS2") (pin "36") (pinfunction "GPIO16_36") (pintype "passive+no_connect"))
    )
    (net (code "71") (name "unconnected-(XS2-GPIO17-Pad11)") (class "Default")
      (node (ref "XS2") (pin "11") (pinfunction "GPIO17_11") (pintype "passive+no_connect"))
    )
    (net (code "72") (name "unconnected-(XS2-GPIO18-Pad12)") (class "Default")
      (node (ref "XS2") (pin "12") (pinfunction "GPIO18_12") (pintype "passive+no_connect"))
    )
    (net (code "73") (name "unconnected-(XS2-GPIO19-Pad35)") (class "Default")
      (node (ref "XS2") (pin "35") (pinfunction "GPIO19_35") (pintype "passive+no_connect"))
    )
    (net (code "74") (name "unconnected-(XS2-GPIO20-Pad38)") (class "Default")
      (node (ref "XS2") (pin "38") (pinfunction "GPIO20_38") (pintype "passive+no_connect"))
    )
    (net (code "75") (name "unconnected-(XS2-GPIO21-Pad40)") (class "Default")
      (node (ref "XS2") (pin "40") (pinfunction "GPIO21_40") (pintype "passive+no_connect"))
    )
    (net (code "76") (name "unconnected-(XS2-GPIO22-Pad15)") (class "Default")
      (node (ref "XS2") (pin "15") (pinfunction "GPIO22_15") (pintype "passive+no_connect"))
    )
    (net (code "77") (name "unconnected-(XS2-GPIO22-Pad22)") (class "Default")
      (node (ref "XS2") (pin "22") (pinfunction "GPIO22_22") (pintype "passive+no_connect"))
    )
    (net (code "78") (name "unconnected-(XS2-GPIO23-Pad16)") (class "Default")
      (node (ref "XS2") (pin "16") (pinfunction "GPIO23_16") (pintype "passive+no_connect"))
    )
    (net (code "79") (name "unconnected-(XS2-GPIO24-Pad18)") (class "Default")
      (node (ref "XS2") (pin "18") (pinfunction "GPIO24_18") (pintype "passive+no_connect"))
    )
    (net (code "80") (name "unconnected-(XS2-GPIO26-Pad37)") (class "Default")
      (node (ref "XS2") (pin "37") (pinfunction "GPIO26_37") (pintype "passive+no_connect"))
    )
    (net (code "81") (name "unconnected-(XS2-GPIO27-Pad13)") (class "Default")
      (node (ref "XS2") (pin "13") (pinfunction "GPIO27_13") (pintype "passive+no_connect"))
    )
    (net (code "82") (name "unconnected-(XS2-ID_SC-Pad28)") (class "Default")
      (node (ref "XS2") (pin "28") (pinfunction "ID_SC_28") (pintype "passive+no_connect"))
    )
    (net (code "83") (name "unconnected-(XS2-ID_SD-Pad27)") (class "Default")
      (node (ref "XS2") (pin "27") (pinfunction "ID_SD_27") (pintype "passive+no_connect"))
    )
  )
)
